# Output_Voltage_Selection_and_Enable.net
KiCad netlist of a schematic drawn in Altium Designer
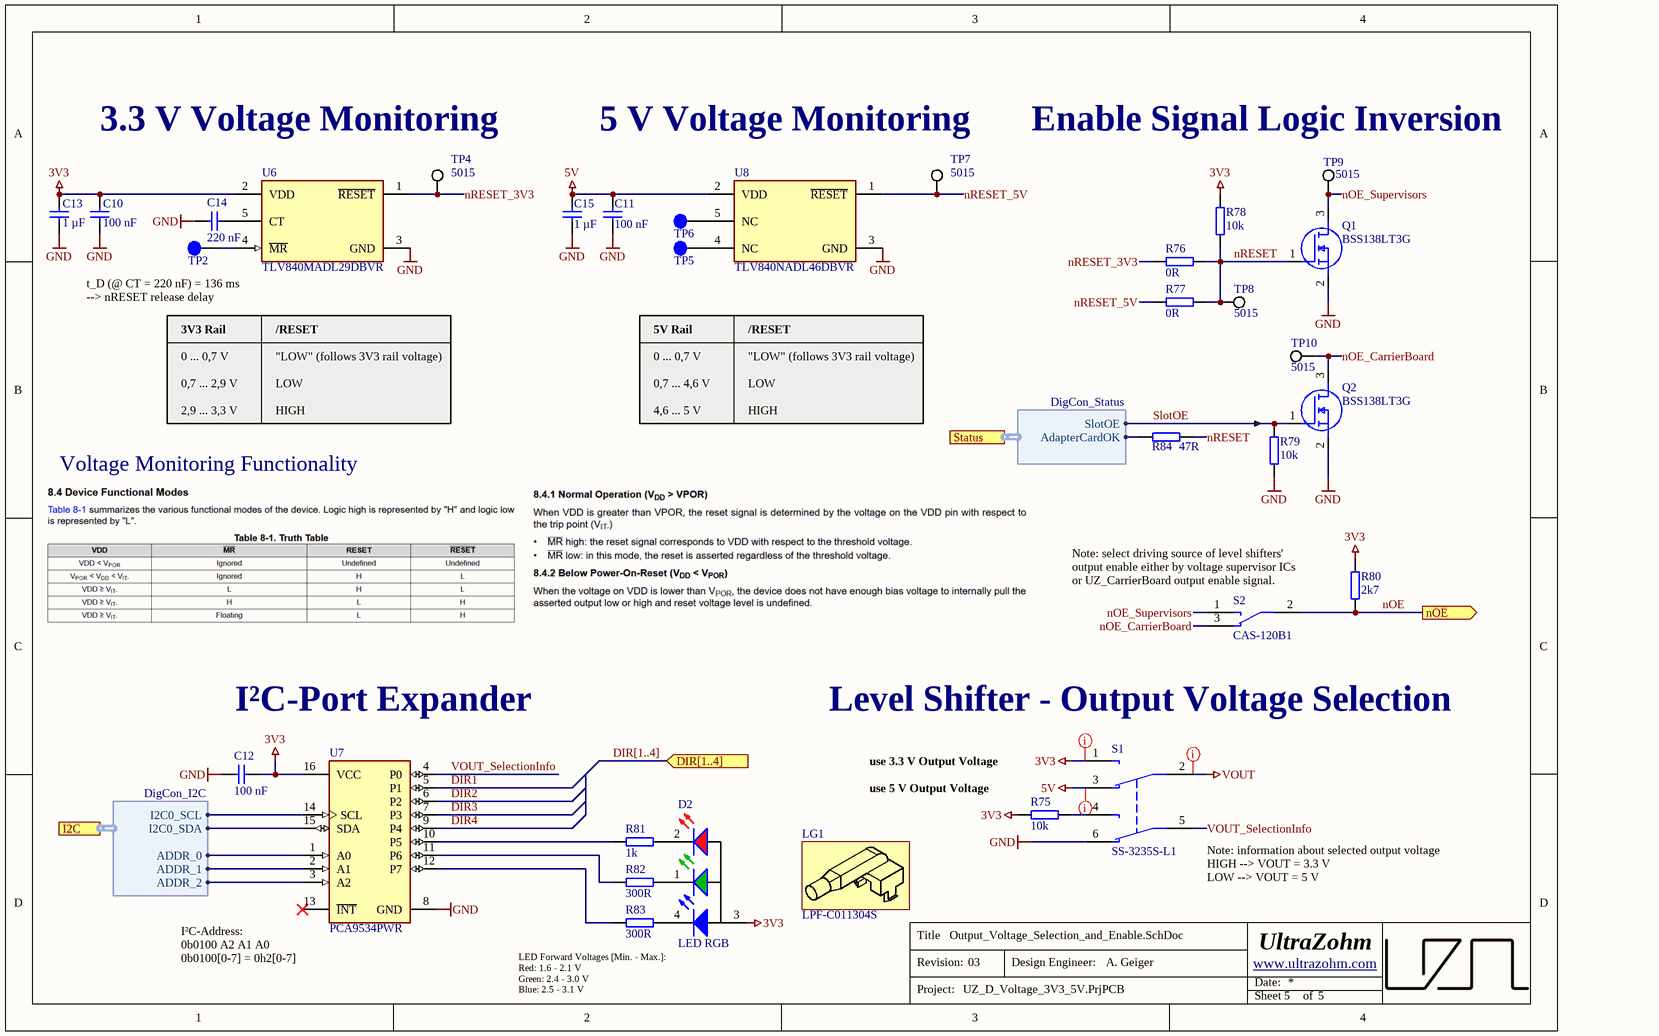
[diagram p0: Output_Voltage_Selection_and_Enable.SchDoc]

(export (version "E")
  (design (tool "Eeschema 10.0.6"))
  (components
    (comp (ref "C10")
      (value "100 nF")
      (footprint "C_0603_TE")
      (description "Generic capacitor")
      (fields
        (field (name "MANUFACTURER PART NUMBER") "UZgen_C_0603_100nF_50V_X7R")
        (field (name "MANUFACTURER") "UZgen")
        (field (name "CREATED FROM") "AGeiger")
      )
      (libsource (lib "user") (part "CAP-NP"))
    )
    (comp (ref "C11")
      (value "100 nF")
      (footprint "C_0603_TE")
      (description "Generic capacitor")
      (fields
        (field (name "MANUFACTURER PART NUMBER") "UZgen_C_0603_100nF_50V_X7R")
        (field (name "MANUFACTURER") "UZgen")
        (field (name "CREATED FROM") "AGeiger")
      )
      (libsource (lib "user") (part "CAP-NP"))
    )
    (comp (ref "C12")
      (value "100 nF")
      (footprint "C_0603_TE")
      (description "Generic capacitor")
      (fields
        (field (name "MANUFACTURER PART NUMBER") "UZgen_C_0603_100nF_50V_X7R")
        (field (name "MANUFACTURER") "UZgen")
        (field (name "CREATED FROM") "AGeiger")
      )
      (libsource (lib "user") (part "CAP-NP"))
    )
    (comp (ref "C13")
      (value "1 µF")
      (footprint "C_0603_TE")
      (description "Generic capacitor")
      (fields
        (field (name "MANUFACTURER PART NUMBER") "UZgen_C_0603_1uF_16V_X7R")
        (field (name "MANUFACTURER") "UZgen")
        (field (name "CREATED FROM") "UZgenTool")
      )
      (libsource (lib "user") (part "CAP-NP"))
    )
    (comp (ref "C14")
      (value "220 nF")
      (footprint "C_0603_TE")
      (description "Generic capacitor")
      (fields
        (field (name "MANUFACTURER PART NUMBER") "UZgen_C_0603_220nF_50V_X7R")
        (field (name "MANUFACTURER") "UZgen")
        (field (name "CREATED FROM") "UZgenTool")
      )
      (libsource (lib "user") (part "CAP-NP"))
    )
    (comp (ref "C15")
      (value "1 µF")
      (footprint "C_0603_TE")
      (description "Generic capacitor")
      (fields
        (field (name "MANUFACTURER PART NUMBER") "UZgen_C_0603_1uF_16V_X7R")
        (field (name "MANUFACTURER") "UZgen")
        (field (name "CREATED FROM") "UZgenTool")
      )
      (libsource (lib "user") (part "CAP-NP"))
    )
    (comp (ref "D2")
      (value "LED RGB")
      (footprint "LED_1615")
      (description "RGB LED - SMD 1615")
      (fields
        (field (name "MANUFACTURER PART NUMBER") "A-SP1943B1GHR6C-C01-2T")
        (field (name "MANUFACTURER") "Amicc")
        (field (name "CREATED FROM") "AGeiger")
      )
      (libsource (lib "user") (part "LED_RGB"))
    )
    (comp (ref "LG1")
      (value "LPF-C011304S")
      (footprint "LPF-C011304S")
      (description "LED Light Pipes RA Light Pipe Clr 2.8mm Round")
      (fields (field (name "MANUFACTURER") "Lumex") (field (name "CREATED FROM") "AGeiger"))
      (libsource (lib "user") (part "LPF-C011304S"))
    )
    (comp (ref "Q1")
      (value "BSS138LT3G")
      (footprint "SOT-23-3")
      (description "Power MOSFET, n-Channel, 200 mA, 50 V")
      (fields
        (field (name "MANUFACTURER") "ON Semicondutor")
        (field (name "LCSC PART NUMBER") "C83790")
        (field (name "CREATED FROM") "MGremer")
      )
      (libsource (lib "user") (part "BSS138LT3G"))
    )
    (comp (ref "Q2")
      (value "BSS138LT3G")
      (footprint "SOT-23-3")
      (description "Power MOSFET, n-Channel, 200 mA, 50 V")
      (fields
        (field (name "MANUFACTURER") "ON Semicondutor")
        (field (name "LCSC PART NUMBER") "C83790")
        (field (name "CREATED FROM") "MGremer")
      )
      (libsource (lib "user") (part "BSS138LT3G"))
    )
    (comp (ref "R75")
      (value "10k")
      (footprint "R_0603_TE")
      (description "Generic resistor")
      (fields
        (field (name "MANUFACTURER PART NUMBER") "UZgen_R_0603_10k")
        (field (name "MANUFACTURER") "UZgen")
        (field (name "CREATED FROM") "AGeiger")
      )
      (libsource (lib "user") (part "RES"))
    )
    (comp (ref "R76")
      (value "0R")
      (footprint "R_0603_TE")
      (description "Generic resistor")
      (fields
        (field (name "MANUFACTURER PART NUMBER") "UZgen_R_0603_0R")
        (field (name "MANUFACTURER") "UZgen")
        (field (name "CREATED FROM") "UZgenTool")
      )
      (libsource (lib "user") (part "RES"))
    )
    (comp (ref "R77")
      (value "0R")
      (footprint "R_0603_TE")
      (description "Generic resistor")
      (fields
        (field (name "MANUFACTURER PART NUMBER") "UZgen_R_0603_0R")
        (field (name "MANUFACTURER") "UZgen")
        (field (name "CREATED FROM") "UZgenTool")
      )
      (libsource (lib "user") (part "RES"))
    )
    (comp (ref "R78")
      (value "10k")
      (footprint "R_0603_TE")
      (description "Generic resistor")
      (fields
        (field (name "MANUFACTURER PART NUMBER") "UZgen_R_0603_10k")
        (field (name "MANUFACTURER") "UZgen")
        (field (name "CREATED FROM") "AGeiger")
      )
      (libsource (lib "user") (part "RES"))
    )
    (comp (ref "R79")
      (value "10k")
      (footprint "R_0603_TE")
      (description "Generic resistor")
      (fields
        (field (name "MANUFACTURER PART NUMBER") "UZgen_R_0603_10k")
        (field (name "MANUFACTURER") "UZgen")
        (field (name "CREATED FROM") "AGeiger")
      )
      (libsource (lib "user") (part "RES"))
    )
    (comp (ref "R80")
      (value "2k7")
      (footprint "R_0603_TE")
      (description "Generic resistor")
      (fields
        (field (name "MANUFACTURER PART NUMBER") "UZgen_R_0603_2k7")
        (field (name "MANUFACTURER") "UZgen")
        (field (name "CREATED FROM") "UZgenTool")
      )
      (libsource (lib "user") (part "RES"))
    )
    (comp (ref "R81")
      (value "1k")
      (footprint "R_0603_TE")
      (description "Generic resistor")
      (fields
        (field (name "MANUFACTURER PART NUMBER") "UZgen_R_0603_1k")
        (field (name "MANUFACTURER") "UZgen")
        (field (name "CREATED FROM") "UZgenTool")
      )
      (libsource (lib "user") (part "RES"))
    )
    (comp (ref "R82")
      (value "300R")
      (footprint "R_0603_TE")
      (description "Generic resistor")
      (fields
        (field (name "MANUFACTURER PART NUMBER") "UZgen_R_0603_300R")
        (field (name "MANUFACTURER") "UZgen")
        (field (name "CREATED FROM") "UZgenTool")
      )
      (libsource (lib "user") (part "RES"))
    )
    (comp (ref "R83")
      (value "300R")
      (footprint "R_0603_TE")
      (description "Generic resistor")
      (fields
        (field (name "MANUFACTURER PART NUMBER") "UZgen_R_0603_300R")
        (field (name "MANUFACTURER") "UZgen")
        (field (name "CREATED FROM") "UZgenTool")
      )
      (libsource (lib "user") (part "RES"))
    )
    (comp (ref "R84")
      (value "47R")
      (footprint "R_0603_TE")
      (description "Generic resistor")
      (fields
        (field (name "MANUFACTURER PART NUMBER") "UZgen_R_0603_47R")
        (field (name "MANUFACTURER") "UZgen")
        (field (name "CREATED FROM") "UZgenTool")
      )
      (libsource (lib "user") (part "RES"))
    )
    (comp (ref "S1")
      (value "SS-3235S-L1")
      (footprint "SS-3235S-L1")
      (description "50mA Horizontal attachment DPDT 12V 12V 50mA 10,000 times Black SMD Slide Switches ROHS")
      (fields
        (field (name "MANUFACTURER") "XKB Connection")
        (field (name "LCSC PART NUMBER") "C500055")
        (field (name "CREATED FROM") "AGeiger")
      )
      (libsource (lib "user") (part "SS-3235S-L1"))
    )
    (comp (ref "S2")
      (value "CAS-120B1")
      (footprint "CAS120B1")
      (fields
        (field (name "MANUFACTURER") "Nidec Components")
        (field (name "LCSC PART NUMBER") "C3664598")
        (field (name "CREATED FROM") "AGeiger")
      )
      (libsource (lib "user") (part "CAS-120B1"))
    )
    (comp (ref "TP2")
      (value "Testpoint 1mm")
      (footprint "TP_1mm")
      (fields
        (field (name "MANUFACTURER PART NUMBER") "NULL")
        (field (name "CREATED") "2018_06_25_AGeiger")
        (field (name "CREATED FROM") "AGeiger")
      )
      (libsource (lib "user") (part "TP_1mm"))
    )
    (comp (ref "TP4")
      (value "5015")
      (footprint "FP-5015-MFG")
      (description "Circuit Board Hardware - PCB SM TEST POINT ON T&R - MINIATURE")
      (fields
        (field (name "MANUFACTURER") "Keystone Electronics")
        (field (name "LCSC PART NUMBER") "C5199798")
        (field (name "CREATED FROM") "AGeiger")
      )
      (libsource (lib "user") (part "SMD Testpoint"))
    )
    (comp (ref "TP5")
      (value "Testpoint 1mm")
      (footprint "TP_1mm")
      (fields
        (field (name "MANUFACTURER PART NUMBER") "NULL")
        (field (name "CREATED") "2018_06_25_AGeiger")
        (field (name "CREATED FROM") "AGeiger")
      )
      (libsource (lib "user") (part "TP_1mm"))
    )
    (comp (ref "TP6")
      (value "Testpoint 1mm")
      (footprint "TP_1mm")
      (fields
        (field (name "MANUFACTURER PART NUMBER") "NULL")
        (field (name "CREATED") "2018_06_25_AGeiger")
        (field (name "CREATED FROM") "AGeiger")
      )
      (libsource (lib "user") (part "TP_1mm"))
    )
    (comp (ref "TP7")
      (value "5015")
      (footprint "FP-5015-MFG")
      (description "Circuit Board Hardware - PCB SM TEST POINT ON T&R - MINIATURE")
      (fields
        (field (name "MANUFACTURER") "Keystone Electronics")
        (field (name "LCSC PART NUMBER") "C5199798")
        (field (name "CREATED FROM") "AGeiger")
      )
      (libsource (lib "user") (part "SMD Testpoint"))
    )
    (comp (ref "TP8")
      (value "5015")
      (footprint "FP-5015-MFG")
      (description "Circuit Board Hardware - PCB SM TEST POINT ON T&R - MINIATURE")
      (fields
        (field (name "MANUFACTURER") "Keystone Electronics")
        (field (name "LCSC PART NUMBER") "C5199798")
        (field (name "CREATED FROM") "AGeiger")
      )
      (libsource (lib "user") (part "SMD Testpoint"))
    )
    (comp (ref "TP9")
      (value "5015")
      (footprint "FP-5015-MFG")
      (description "Circuit Board Hardware - PCB SM TEST POINT ON T&R - MINIATURE")
      (fields
        (field (name "MANUFACTURER") "Keystone Electronics")
        (field (name "LCSC PART NUMBER") "C5199798")
        (field (name "CREATED FROM") "AGeiger")
      )
      (libsource (lib "user") (part "SMD Testpoint"))
    )
    (comp (ref "TP10")
      (value "5015")
      (footprint "FP-5015-MFG")
      (description "Circuit Board Hardware - PCB SM TEST POINT ON T&R - MINIATURE")
      (fields
        (field (name "MANUFACTURER") "Keystone Electronics")
        (field (name "LCSC PART NUMBER") "C5199798")
        (field (name "CREATED FROM") "AGeiger")
      )
      (libsource (lib "user") (part "SMD Testpoint"))
    )
    (comp (ref "U6")
      (value "TLV840MADL29DBVR")
      (footprint "SOT23-5_DBV")
      (description "Supervisory Circuits 2.9V Monitor")
      (fields
        (field (name "MANUFACTURER") "Texas Instruments")
        (field (name "LCSC PART NUMBER") "C3687807")
        (field (name "CREATED FROM") "AGeiger")
      )
      (libsource (lib "user") (part "TLV840-29"))
    )
    (comp (ref "U7")
      (value "PCA9534PWR")
      (footprint "TSSOP-16_PW0016A_N")
      (description "8-bit 2.3- to 5.5-V I2C/SMBus I/O expander with interrupt & config registers")
      (fields
        (field (name "MANUFACTURER") "Texas Instruments")
        (field (name "LCSC PART NUMBER") "C133803")
        (field (name "CREATED FROM") "AGeiger")
      )
      (libsource (lib "user") (part "PCA9534"))
    )
    (comp (ref "U8")
      (value "TLV840NADL46DBVR")
      (footprint "SOT23-5_DBV")
      (description "Supervisory Circuits 4.6V Monitor")
      (fields
        (field (name "MANUFACTURER") "Texas Instruments")
        (field (name "LCSC PART NUMBER") "C2870132")
        (field (name "CREATED FROM") "AGeiger")
      )
      (libsource (lib "user") (part "TLV840-46"))
    )
  )
  (nets
    (net (code "3") (name "/ADDR_0") (class "Default")
      (node (ref "U7") (pin "1") (pinfunction "A0_1") (pintype "input"))
    )
    (net (code "4") (name "/ADDR_1") (class "Default")
      (node (ref "U7") (pin "2") (pinfunction "A1_2") (pintype "input"))
    )
    (net (code "5") (name "/ADDR_2") (class "Default")
      (node (ref "U7") (pin "3") (pinfunction "A2_3") (pintype "input"))
    )
    (net (code "6") (name "/AdapterCardOK") (class "Default")
      (node (ref "R84") (pin "1") (pinfunction "1_1") (pintype "passive"))
    )
    (net (code "7") (name "/DIR1") (class "Default")
      (node (ref "U7") (pin "5") (pinfunction "P1_5") (pintype "bidirectional"))
    )
    (net (code "8") (name "/DIR2") (class "Default")
      (node (ref "U7") (pin "6") (pinfunction "P2_6") (pintype "bidirectional"))
    )
    (net (code "9") (name "/DIR3") (class "Default")
      (node (ref "U7") (pin "7") (pinfunction "P3_7") (pintype "bidirectional"))
    )
    (net (code "10") (name "/DIR4") (class "Default")
      (node (ref "U7") (pin "9") (pinfunction "P4_9") (pintype "bidirectional"))
    )
    (net (code "12") (name "/I2C0_SCL") (class "Default")
      (node (ref "U7") (pin "14") (pinfunction "SCL_14") (pintype "input"))
    )
    (net (code "13") (name "/I2C0_SDA") (class "Default")
      (node (ref "U7") (pin "15") (pinfunction "SDA_15") (pintype "bidirectional"))
    )
    (net (code "14") (name "/SlotOE") (class "Default")
      (node (ref "Q2") (pin "1") (pinfunction "G_1") (pintype "passive"))
      (node (ref "R79") (pin "2") (pinfunction "2_2") (pintype "passive"))
    )
    (net (code "15") (name "/VOUT_SelectionInfo") (class "Default")
      (node (ref "S1") (pin "5") (pinfunction "COM2_5") (pintype "passive"))
      (node (ref "U7") (pin "4") (pinfunction "P0_4") (pintype "bidirectional"))
    )
    (net (code "16") (name "/nOE") (class "Default")
      (node (ref "R80") (pin "1") (pinfunction "1_1") (pintype "passive"))
      (node (ref "S2") (pin "2") (pinfunction "COM1_2") (pintype "passive"))
    )
    (net (code "17") (name "/nOE_CarrierBoard") (class "Default")
      (node (ref "Q2") (pin "3") (pinfunction "D_3") (pintype "passive"))
      (node (ref "S2") (pin "3") (pinfunction "NC1_3") (pintype "passive"))
      (node (ref "TP10") (pin "1") (pinfunction "1_1") (pintype "passive"))
    )
    (net (code "18") (name "/nOE_Supervisors") (class "Default")
      (node (ref "Q1") (pin "3") (pinfunction "D_3") (pintype "passive"))
      (node (ref "S2") (pin "1") (pinfunction "NO1_1") (pintype "passive"))
      (node (ref "TP9") (pin "1") (pinfunction "1_1") (pintype "passive"))
    )
    (net (code "19") (name "/nRESET") (class "Default")
      (node (ref "Q1") (pin "1") (pinfunction "G_1") (pintype "passive"))
      (node (ref "R76") (pin "2") (pinfunction "2_2") (pintype "passive"))
      (node (ref "R77") (pin "2") (pinfunction "2_2") (pintype "passive"))
      (node (ref "R78") (pin "1") (pinfunction "1_1") (pintype "passive"))
      (node (ref "R84") (pin "2") (pinfunction "2_2") (pintype "passive"))
      (node (ref "TP8") (pin "1") (pinfunction "1_1") (pintype "passive"))
    )
    (net (code "20") (name "/nRESET_3V3") (class "Default")
      (node (ref "R76") (pin "1") (pinfunction "1_1") (pintype "passive"))
      (node (ref "TP4") (pin "1") (pinfunction "1_1") (pintype "passive"))
      (node (ref "U6") (pin "1") (pinfunction "~{RESET}_1") (pintype "open_collector"))
    )
    (net (code "21") (name "/nRESET_5V") (class "Default")
      (node (ref "R77") (pin "1") (pinfunction "1_1") (pintype "passive"))
      (node (ref "TP7") (pin "1") (pinfunction "1_1") (pintype "passive"))
      (node (ref "U8") (pin "1") (pinfunction "~{RESET}_1") (pintype "open_collector"))
    )
    (net (code "24") (name "3V3") (class "Default")
      (node (ref "C10") (pin "1") (pinfunction "1_1") (pintype "passive"))
      (node (ref "C12") (pin "2") (pinfunction "2_2") (pintype "passive"))
      (node (ref "C13") (pin "2") (pinfunction "2_2") (pintype "passive"))
      (node (ref "D2") (pin "3") (pinfunction "A_3") (pintype "passive"))
      (node (ref "R75") (pin "2") (pinfunction "2_2") (pintype "passive"))
      (node (ref "R78") (pin "2") (pinfunction "2_2") (pintype "passive"))
      (node (ref "R80") (pin "2") (pinfunction "2_2") (pintype "passive"))
      (node (ref "S1") (pin "1") (pinfunction "NO1_1") (pintype "passive"))
      (node (ref "U6") (pin "2") (pinfunction "VDD_2") (pintype "power_in"))
      (node (ref "U7") (pin "16") (pinfunction "VCC_16") (pintype "power_in"))
    )
    (net (code "25") (name "5V") (class "Default")
      (node (ref "C11") (pin "1") (pinfunction "1_1") (pintype "passive"))
      (node (ref "C15") (pin "2") (pinfunction "2_2") (pintype "passive"))
      (node (ref "S1") (pin "3") (pinfunction "NC1_3") (pintype "passive"))
      (node (ref "U8") (pin "2") (pinfunction "VDD_2") (pintype "power_in"))
    )
    (net (code "26") (name "GND") (class "Default")
      (node (ref "C10") (pin "2") (pinfunction "2_2") (pintype "passive"))
      (node (ref "C11") (pin "2") (pinfunction "2_2") (pintype "passive"))
      (node (ref "C12") (pin "1") (pinfunction "1_1") (pintype "passive"))
      (node (ref "C13") (pin "1") (pinfunction "1_1") (pintype "passive"))
      (node (ref "C14") (pin "1") (pinfunction "1_1") (pintype "passive"))
      (node (ref "C15") (pin "1") (pinfunction "1_1") (pintype "passive"))
      (node (ref "Q1") (pin "2") (pinfunction "S_2") (pintype "passive"))
      (node (ref "Q2") (pin "2") (pinfunction "S_2") (pintype "passive"))
      (node (ref "R79") (pin "1") (pinfunction "1_1") (pintype "passive"))
      (node (ref "S1") (pin "6") (pinfunction "NC2_6") (pintype "passive"))
      (node (ref "U6") (pin "3") (pinfunction "GND_3") (pintype "power_in"))
      (node (ref "U7") (pin "8") (pinfunction "GND_8") (pintype "power_in"))
      (node (ref "U8") (pin "3") (pinfunction "GND_3") (pintype "power_in"))
    )
    (net (code "27") (name "Net-(D2-K-Pad1)") (class "Default")
      (node (ref "D2") (pin "1") (pinfunction "K_1") (pintype "passive"))
      (node (ref "R82") (pin "2") (pinfunction "2_2") (pintype "passive"))
    )
    (net (code "28") (name "Net-(D2-K-Pad2)") (class "Default")
      (node (ref "D2") (pin "2") (pinfunction "K_2") (pintype "passive"))
      (node (ref "R81") (pin "1") (pinfunction "1_1") (pintype "passive"))
    )
    (net (code "29") (name "Net-(D2-K_B)") (class "Default")
      (node (ref "D2") (pin "4") (pinfunction "K_B_4") (pintype "passive"))
      (node (ref "R83") (pin "2") (pinfunction "2_2") (pintype "passive"))
    )
    (net (code "30") (name "Net-(S1-NO2)") (class "Default")
      (node (ref "R75") (pin "1") (pinfunction "1_1") (pintype "passive"))
      (node (ref "S1") (pin "4") (pinfunction "NO2_4") (pintype "passive"))
    )
    (net (code "31") (name "Net-(TP5-Pad1)") (class "Default")
      (node (ref "TP5") (pin "1") (pintype "passive"))
      (node (ref "U8") (pin "4") (pinfunction "NC_4") (pintype "passive"))
    )
    (net (code "32") (name "Net-(TP6-Pad1)") (class "Default")
      (node (ref "TP6") (pin "1") (pintype "passive"))
      (node (ref "U8") (pin "5") (pinfunction "NC_5") (pintype "passive"))
    )
    (net (code "33") (name "Net-(U6-CT)") (class "Default")
      (node (ref "C14") (pin "2") (pinfunction "2_2") (pintype "passive"))
      (node (ref "U6") (pin "5") (pinfunction "CT_5") (pintype "passive"))
    )
    (net (code "34") (name "Net-(U6-~{MR})") (class "Default")
      (node (ref "TP2") (pin "1") (pintype "passive"))
      (node (ref "U6") (pin "4") (pinfunction "~{MR}_4") (pintype "input"))
    )
    (net (code "35") (name "Net-(U7-P5)") (class "Default")
      (node (ref "R81") (pin "2") (pinfunction "2_2") (pintype "passive"))
      (node (ref "U7") (pin "10") (pinfunction "P5_10") (pintype "bidirectional"))
    )
    (net (code "36") (name "Net-(U7-P6)") (class "Default")
      (node (ref "R82") (pin "1") (pinfunction "1_1") (pintype "passive"))
      (node (ref "U7") (pin "11") (pinfunction "P6_11") (pintype "bidirectional"))
    )
    (net (code "37") (name "Net-(U7-P7)") (class "Default")
      (node (ref "R83") (pin "1") (pinfunction "1_1") (pintype "passive"))
      (node (ref "U7") (pin "12") (pinfunction "P7_12") (pintype "bidirectional"))
    )
    (net (code "38") (name "VOUT") (class "Default")
      (node (ref "S1") (pin "2") (pinfunction "COM1_2") (pintype "passive"))
    )
    (net (code "39") (name "unconnected-(U7-~{INT}-Pad13)") (class "Default")
      (node (ref "U7") (pin "13") (pinfunction "~{INT}_13") (pintype "open_collector+no_connect"))
    )
  )
)
